# Moty_Light.net
KiCad netlist of a schematic drawn in EAGLE
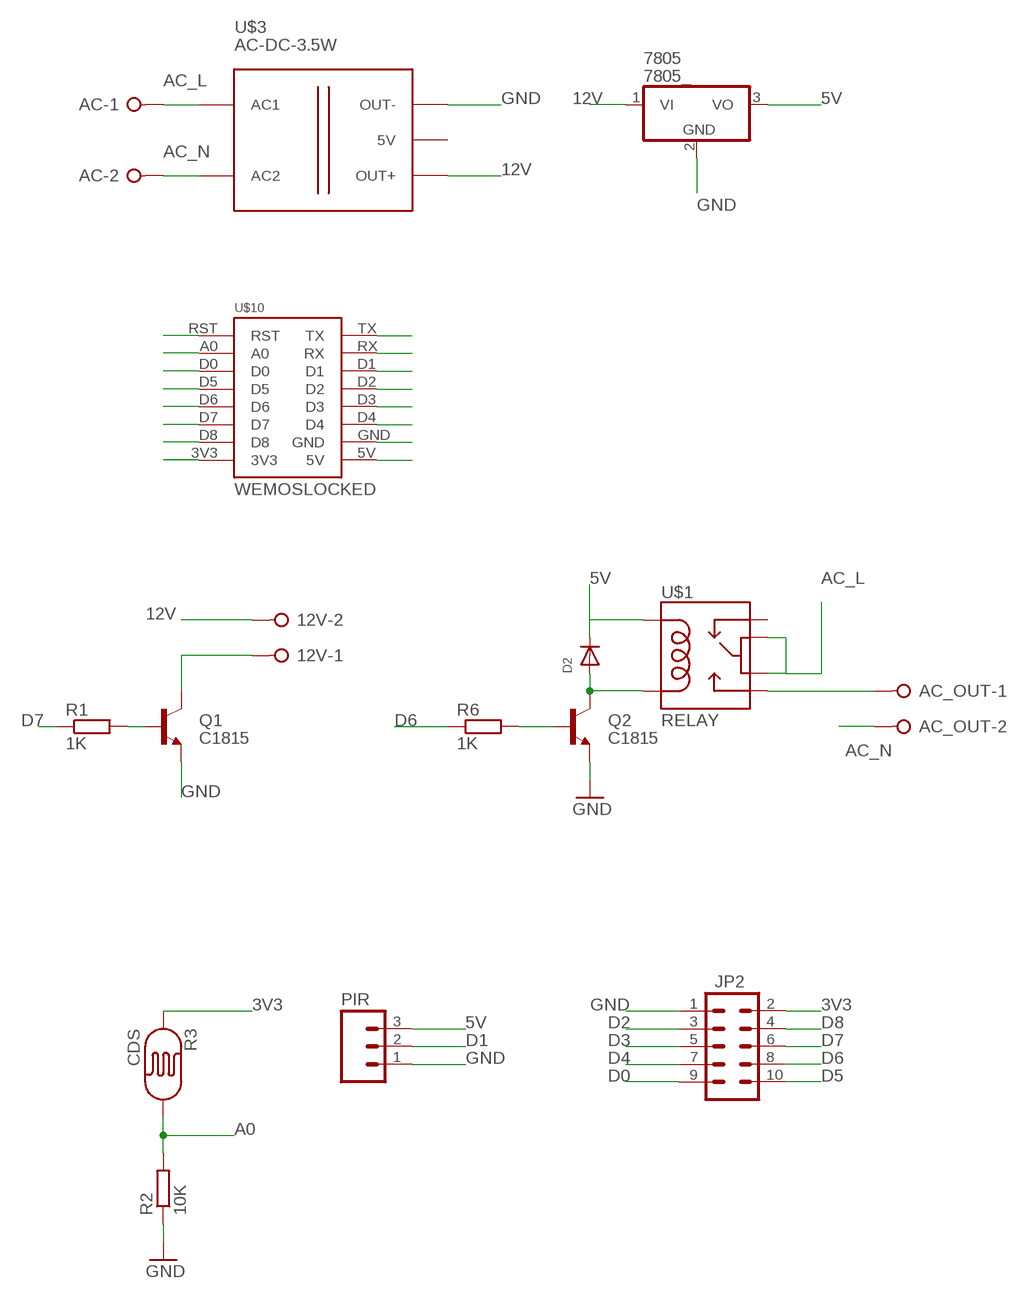
[diagram p0: schematic, sheet 1]

(export (version "E")
  (design (tool "Eeschema 10.0.6"))
  (components
    (comp (ref "12V")
      (value "W237-02P")
      (footprint "eagle-import:W237-132")
      (libsource (lib "eagle-import") (part "W237-02P"))
    )
    (comp (ref "7805")
      (value "7805_")
      (footprint "eagle-import:TO220V")
      (libsource (lib "eagle-import") (part "78TV05"))
    )
    (comp (ref "AC")
      (value "W237-02P")
      (footprint "eagle-import:W237-132")
      (libsource (lib "eagle-import") (part "W237-02P"))
    )
    (comp (ref "AC_OUT")
      (value "W237-02P")
      (footprint "eagle-import:W237-132")
      (libsource (lib "eagle-import") (part "W237-02P"))
    )
    (comp (ref "D2")
      (value "DIODESMA")
      (footprint "eagle-import:SMADIODE")
      (libsource (lib "eagle-import") (part "DIODESMA"))
    )
    (comp (ref "JP2")
      (value "M05X2PTH")
      (footprint "eagle-import:AVR_ICSP")
      (libsource (lib "eagle-import") (part "M05X2PTH"))
    )
    (comp (ref "PIR")
      (value "M03PTH")
      (footprint "eagle-import:1X03")
      (libsource (lib "eagle-import") (part "M03PTH"))
    )
    (comp (ref "Q1")
      (value "C1815")
      (footprint "eagle-import:SOT23-3")
      (libsource (lib "eagle-import") (part "TRANSISTOR_NPNMMBT2222A"))
    )
    (comp (ref "Q2")
      (value "C1815")
      (footprint "eagle-import:SOT23-3")
      (libsource (lib "eagle-import") (part "TRANSISTOR_NPNMMBT2222A"))
    )
    (comp (ref "R1")
      (value "1K")
      (footprint "eagle-import:R0805")
      (libsource (lib "eagle-import") (part "R-EU_R0805"))
    )
    (comp (ref "R2")
      (value "10K")
      (footprint "eagle-import:R0805")
      (libsource (lib "eagle-import") (part "R-EU_R0805"))
    )
    (comp (ref "R3")
      (value "CDS")
      (footprint "eagle-import:PHOTOCELL_THIN")
      (libsource (lib "eagle-import") (part "PHOTOCELL"))
    )
    (comp (ref "R6")
      (value "1K")
      (footprint "eagle-import:R0805")
      (libsource (lib "eagle-import") (part "R-EU_R0805"))
    )
    (comp (ref "U$1")
      (value "RELAY")
      (footprint "eagle-import:MINIATURE_RELAY_JRC_21F")
      (libsource (lib "eagle-import") (part "MINIATURE_RELAY_JRC_21F"))
    )
    (comp (ref "U$3")
      (value "AC-DC-3.5W")
      (footprint "eagle-import:AC-DC-3.5W")
      (libsource (lib "eagle-import") (part "AC-DC-3.5W"))
    )
    (comp (ref "U$10")
      (value "WEMOSLOCKED")
      (footprint "eagle-import:WEMOS_LOCKED")
      (libsource (lib "eagle-import") (part "WEMOSLOCKED"))
    )
  )
  (nets
    (net (code "1") (name "/3V3") (class "Default")
      (node (ref "JP2") (pin "2") (pinfunction "2_2") (pintype "passive"))
      (node (ref "R3") (pin "1") (pinfunction "P$1_1") (pintype "bidirectional"))
      (node (ref "U$10") (pin "3V3") (pinfunction "3V3_3V3") (pintype "bidirectional"))
    )
    (net (code "2") (name "/5V") (class "Default")
      (node (ref "7805") (pin "3") (pinfunction "VO_3") (pintype "passive"))
      (node (ref "D2") (pin "C") (pinfunction "C_C") (pintype "passive"))
      (node (ref "PIR") (pin "3") (pinfunction "3_3") (pintype "passive"))
      (node (ref "U$1") (pin "COIL1") (pinfunction "COIL1_COIL1") (pintype "bidirectional"))
      (node (ref "U$10") (pin "5V") (pinfunction "5V_5V") (pintype "bidirectional"))
    )
    (net (code "3") (name "/12V") (class "Default")
      (node (ref "12V") (pin "2") (pinfunction "KL_2") (pintype "passive"))
      (node (ref "7805") (pin "1") (pinfunction "VI_1") (pintype "input"))
      (node (ref "U$3") (pin "J2.3") (pinfunction "OUT+_J2.3") (pintype "bidirectional"))
    )
    (net (code "4") (name "/A0") (class "Default")
      (node (ref "R2") (pin "2") (pinfunction "2_2") (pintype "passive"))
      (node (ref "R3") (pin "2") (pinfunction "P$2_2") (pintype "bidirectional"))
      (node (ref "U$10") (pin "A0") (pinfunction "A0_A0") (pintype "bidirectional"))
    )
    (net (code "5") (name "/AC_L") (class "Default")
      (node (ref "AC") (pin "1") (pinfunction "KL_1") (pintype "passive"))
      (node (ref "U$1") (pin "COM1") (pinfunction "COM1_COM1") (pintype "bidirectional"))
      (node (ref "U$1") (pin "COM2") (pinfunction "COM2_COM2") (pintype "bidirectional"))
      (node (ref "U$3") (pin "J1.1") (pinfunction "AC1_J1.1") (pintype "bidirectional"))
    )
    (net (code "6") (name "/AC_N") (class "Default")
      (node (ref "AC") (pin "2") (pinfunction "KL_2") (pintype "passive"))
      (node (ref "AC_OUT") (pin "2") (pinfunction "KL_2") (pintype "passive"))
      (node (ref "U$3") (pin "J1.2") (pinfunction "AC2_J1.2") (pintype "bidirectional"))
    )
    (net (code "7") (name "/D0") (class "Default")
      (node (ref "JP2") (pin "9") (pinfunction "9_9") (pintype "passive"))
      (node (ref "U$10") (pin "D0") (pinfunction "D0_D0") (pintype "bidirectional"))
    )
    (net (code "8") (name "/D1") (class "Default")
      (node (ref "PIR") (pin "2") (pinfunction "2_2") (pintype "passive"))
      (node (ref "U$10") (pin "D1") (pinfunction "D1_D1") (pintype "bidirectional"))
    )
    (net (code "9") (name "/D2") (class "Default")
      (node (ref "JP2") (pin "3") (pinfunction "3_3") (pintype "passive"))
      (node (ref "U$10") (pin "D2") (pinfunction "D2_D2") (pintype "bidirectional"))
    )
    (net (code "10") (name "/D3") (class "Default")
      (node (ref "JP2") (pin "5") (pinfunction "5_5") (pintype "passive"))
      (node (ref "U$10") (pin "D3") (pinfunction "D3_D3") (pintype "bidirectional"))
    )
    (net (code "11") (name "/D4") (class "Default")
      (node (ref "JP2") (pin "7") (pinfunction "7_7") (pintype "passive"))
      (node (ref "U$10") (pin "D4") (pinfunction "D4_D4") (pintype "bidirectional"))
    )
    (net (code "12") (name "/D5") (class "Default")
      (node (ref "JP2") (pin "10") (pinfunction "10_10") (pintype "passive"))
      (node (ref "U$10") (pin "D5") (pinfunction "D5_D5") (pintype "bidirectional"))
    )
    (net (code "13") (name "/D6") (class "Default")
      (node (ref "JP2") (pin "8") (pinfunction "8_8") (pintype "passive"))
      (node (ref "R6") (pin "1") (pinfunction "1_1") (pintype "passive"))
      (node (ref "U$10") (pin "D6") (pinfunction "D6_D6") (pintype "bidirectional"))
    )
    (net (code "14") (name "/D7") (class "Default")
      (node (ref "JP2") (pin "6") (pinfunction "6_6") (pintype "passive"))
      (node (ref "R1") (pin "1") (pinfunction "1_1") (pintype "passive"))
      (node (ref "U$10") (pin "D7") (pinfunction "D7_D7") (pintype "bidirectional"))
    )
    (net (code "15") (name "/D8") (class "Default")
      (node (ref "JP2") (pin "4") (pinfunction "4_4") (pintype "passive"))
      (node (ref "U$10") (pin "D8") (pinfunction "D8_D8") (pintype "bidirectional"))
    )
    (net (code "16") (name "GND") (class "Default")
      (node (ref "7805") (pin "2") (pinfunction "GND_2") (pintype "passive"))
      (node (ref "JP2") (pin "1") (pinfunction "1_1") (pintype "passive"))
      (node (ref "PIR") (pin "1") (pinfunction "1_1") (pintype "passive"))
      (node (ref "Q1") (pin "2") (pinfunction "E_2") (pintype "passive"))
      (node (ref "Q2") (pin "2") (pinfunction "E_2") (pintype "passive"))
      (node (ref "R2") (pin "1") (pinfunction "1_1") (pintype "passive"))
      (node (ref "U$10") (pin "GND") (pinfunction "GND_GND") (pintype "bidirectional"))
      (node (ref "U$3") (pin "J2.1") (pinfunction "OUT-_J2.1") (pintype "bidirectional"))
    )
    (net (code "17") (name "Net-(12VA-KL)") (class "Default")
      (node (ref "12V") (pin "1") (pinfunction "KL_1") (pintype "passive"))
      (node (ref "Q1") (pin "3") (pinfunction "C_3") (pintype "passive"))
    )
    (net (code "18") (name "Net-(AC_OUTA-KL)") (class "Default")
      (node (ref "AC_OUT") (pin "1") (pinfunction "KL_1") (pintype "passive"))
      (node (ref "U$1") (pin "NO") (pinfunction "NO_NO") (pintype "bidirectional"))
    )
    (net (code "19") (name "Net-(Q1-B)") (class "Default")
      (node (ref "Q1") (pin "1") (pinfunction "B_1") (pintype "passive"))
      (node (ref "R1") (pin "2") (pinfunction "2_2") (pintype "passive"))
    )
    (net (code "20") (name "Net-(Q2-B)") (class "Default")
      (node (ref "Q2") (pin "1") (pinfunction "B_1") (pintype "passive"))
      (node (ref "R6") (pin "2") (pinfunction "2_2") (pintype "passive"))
    )
    (net (code "21") (name "Net-(Q2-C)") (class "Default")
      (node (ref "D2") (pin "A") (pinfunction "A_A") (pintype "passive"))
      (node (ref "Q2") (pin "3") (pinfunction "C_3") (pintype "passive"))
      (node (ref "U$1") (pin "COIL2") (pinfunction "COIL2_COIL2") (pintype "bidirectional"))
    )
    (net (code "22") (name "unconnected-(U$1-PadNC)") (class "Default")
      (node (ref "U$1") (pin "NC") (pinfunction "NC_NC") (pintype "bidirectional"))
    )
    (net (code "23") (name "unconnected-(U$3-5V-PadJ2.2)") (class "Default")
      (node (ref "U$3") (pin "J2.2") (pinfunction "5V_J2.2") (pintype "bidirectional"))
    )
    (net (code "24") (name "unconnected-(U$10-PadRST)") (class "Default")
      (node (ref "U$10") (pin "RST") (pinfunction "RST_RST") (pintype "bidirectional"))
    )
    (net (code "25") (name "unconnected-(U$10-PadRX)") (class "Default")
      (node (ref "U$10") (pin "RX") (pinfunction "RX_RX") (pintype "bidirectional"))
    )
    (net (code "26") (name "unconnected-(U$10-PadTX)") (class "Default")
      (node (ref "U$10") (pin "TX") (pinfunction "TX_TX") (pintype "bidirectional"))
    )
  )
)
